# TP1_NodoWiFi_Pwr_Rev0.net
KiCad netlist of a schematic drawn in Altium Designer
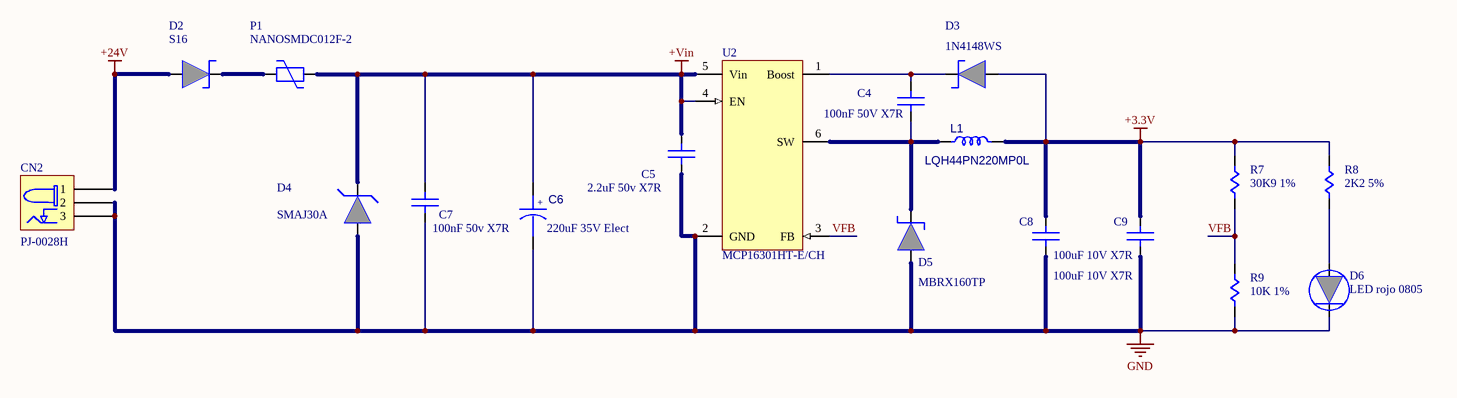
[diagram p0: TP1_NodoWiFi_Pwr_Rev0.SchDoc]

(export (version "E")
  (design (tool "Eeschema 10.0.6"))
  (components
    (comp (ref "C4")
      (value "100nF 50V X7R")
      (footprint "C_0805")
      (description "capacitor no polarizado")
      (libsource (lib "WifiNode") (part "Capacitor_NoP"))
    )
    (comp (ref "C5")
      (value "2.2uF 50v X7R")
      (footprint "C_0805")
      (description "capacitor no polarizado")
      (libsource (lib "WifiNode") (part "Capacitor_NoP"))
    )
    (comp (ref "C6")
      (value "220uF 35V Elect")
      (description "Polarized Capacitor")
      (libsource (lib "WifiNode") (part "CAP_P"))
    )
    (comp (ref "C7")
      (value "100nF 50v X7R")
      (footprint "C_0805")
      (description "capacitor no polarizado")
      (libsource (lib "WifiNode") (part "Capacitor_NoP"))
    )
    (comp (ref "C8")
      (value "100uF 10V X7R")
      (footprint "C_0805")
      (description "capacitor no polarizado")
      (libsource (lib "WifiNode") (part "Capacitor_NoP"))
    )
    (comp (ref "C9")
      (value "100uF 10V X7R")
      (footprint "C_0805")
      (description "capacitor no polarizado")
      (libsource (lib "WifiNode") (part "Capacitor_NoP"))
    )
    (comp (ref "CN2")
      (value "PJ-0028H")
      (footprint "PJ-002BH")
      (description "Conector PJ")
      (libsource (lib "WifiNode") (part "PJ-0028H"))
    )
    (comp (ref "D2")
      (value "S16")
      (footprint "Diode SOD-123")
      (description "Schottky")
      (libsource (lib "WifiNode") (part "Diodo Schottky"))
    )
    (comp (ref "D3")
      (value "1N4148WS")
      (footprint "Diode SOD-323")
      (description "Schottky")
      (libsource (lib "WifiNode") (part "Diodo Schottky"))
    )
    (comp (ref "D4")
      (value "SMAJ30A")
      (footprint "DO-214AC")
      (description "Zener")
      (libsource (lib "WifiNode") (part "Diodo Zener"))
    )
    (comp (ref "D5")
      (value "MBRX160TP")
      (footprint "Diode SOD-123")
      (description "Schottky")
      (libsource (lib "WifiNode") (part "Diodo Schottky"))
    )
    (comp (ref "D6")
      (value "LED rojo 0805")
      (footprint "D_0805")
      (description "LED")
      (libsource (lib "WifiNode") (part "Diodo LED"))
    )
    (comp (ref "L1")
      (value "LQH44PN220MP0L")
      (description "Inductor")
      (libsource (lib "WifiNode") (part "IND"))
    )
    (comp (ref "P1")
      (value "NANOSMDC012F-2")
      (footprint "Polyswitch 1206")
      (description "Poly Switch")
      (libsource (lib "WifiNode") (part "Poly Switch"))
    )
    (comp (ref "R7")
      (value "30K9 1%")
      (footprint "R_0805")
      (description "Resistor")
      (libsource (lib "WifiNode") (part "Resistencia"))
    )
    (comp (ref "R8")
      (value "2K2 5%")
      (footprint "R_0805")
      (description "Resistor")
      (libsource (lib "WifiNode") (part "Resistencia"))
    )
    (comp (ref "R9")
      (value "10K 1%")
      (footprint "R_0805")
      (description "Resistor")
      (libsource (lib "WifiNode") (part "Resistencia"))
    )
    (comp (ref "U2")
      (value "MCP16301HT-E/CH")
      (footprint "IC SOT23-6")
      (description "IC_DC/DC Buck controler")
      (libsource (lib "WifiNode") (part "MCP16301"))
    )
  )
  (nets
    (net (code "1") (name "+3.3V") (class "Default")
      (node (ref "C8") (pin "2") (pinfunction "Cap_2") (pintype "passive"))
      (node (ref "C9") (pin "2") (pinfunction "Cap_2") (pintype "passive"))
      (node (ref "D3") (pin "1") (pinfunction "Cap_1") (pintype "passive"))
      (node (ref "L1") (pin "2") (pinfunction "2_2") (pintype "passive"))
      (node (ref "R7") (pin "2") (pinfunction "Cap_2") (pintype "passive"))
      (node (ref "R8") (pin "2") (pinfunction "Cap_2") (pintype "passive"))
    )
    (net (code "2") (name "+24V") (class "Default")
      (node (ref "CN2") (pin "1") (pinfunction "1_1") (pintype "power_in"))
      (node (ref "D2") (pin "1") (pinfunction "Cap_1") (pintype "passive"))
    )
    (net (code "3") (name "+Vin") (class "Default")
      (node (ref "C5") (pin "2") (pinfunction "Cap_2") (pintype "passive"))
      (node (ref "C6") (pin "1") (pinfunction "1_1") (pintype "passive"))
      (node (ref "C7") (pin "2") (pinfunction "Cap_2") (pintype "passive"))
      (node (ref "D4") (pin "2") (pinfunction "Cap_2") (pintype "passive"))
      (node (ref "P1") (pin "1") (pinfunction "Cap_1") (pintype "passive"))
      (node (ref "U2") (pin "4") (pinfunction "EN_4") (pintype "input"))
      (node (ref "U2") (pin "5") (pinfunction "Vin_5") (pintype "power_in"))
    )
    (net (code "4") (name "/VFB") (class "Default")
      (node (ref "R7") (pin "1") (pinfunction "Cap_1") (pintype "passive"))
      (node (ref "R9") (pin "2") (pinfunction "Cap_2") (pintype "passive"))
      (node (ref "U2") (pin "3") (pinfunction "FB_3") (pintype "input"))
    )
    (net (code "5") (name "GND") (class "Default")
      (node (ref "C5") (pin "1") (pinfunction "Cap_1") (pintype "passive"))
      (node (ref "C6") (pin "2") (pinfunction "2_2") (pintype "passive"))
      (node (ref "C7") (pin "1") (pinfunction "Cap_1") (pintype "passive"))
      (node (ref "C8") (pin "1") (pinfunction "Cap_1") (pintype "passive"))
      (node (ref "C9") (pin "1") (pinfunction "Cap_1") (pintype "passive"))
      (node (ref "CN2") (pin "2") (pinfunction "2_2") (pintype "power_in"))
      (node (ref "CN2") (pin "3") (pinfunction "3_3") (pintype "power_in"))
      (node (ref "D4") (pin "1") (pinfunction "Cap_1") (pintype "passive"))
      (node (ref "D5") (pin "1") (pinfunction "Cap_1") (pintype "passive"))
      (node (ref "D6") (pin "2") (pinfunction "Cap_2") (pintype "passive"))
      (node (ref "R9") (pin "1") (pinfunction "Cap_1") (pintype "passive"))
      (node (ref "U2") (pin "2") (pinfunction "GND_2") (pintype "power_in"))
    )
    (net (code "6") (name "Net-(D2-Cap-Pad2)") (class "Default")
      (node (ref "D2") (pin "2") (pinfunction "Cap_2") (pintype "passive"))
      (node (ref "P1") (pin "2") (pinfunction "Cap_2") (pintype "passive"))
    )
    (net (code "7") (name "Net-(D6-Cap-Pad1)") (class "Default")
      (node (ref "D6") (pin "1") (pinfunction "Cap_1") (pintype "passive"))
      (node (ref "R8") (pin "1") (pinfunction "Cap_1") (pintype "passive"))
    )
    (net (code "8") (name "Net-(U2-Boost)") (class "Default")
      (node (ref "C4") (pin "2") (pinfunction "Cap_2") (pintype "passive"))
      (node (ref "D3") (pin "2") (pinfunction "Cap_2") (pintype "passive"))
      (node (ref "U2") (pin "1") (pinfunction "Boost_1") (pintype "passive"))
    )
    (net (code "9") (name "Net-(U2-SW)") (class "Default")
      (node (ref "C4") (pin "1") (pinfunction "Cap_1") (pintype "passive"))
      (node (ref "D5") (pin "2") (pinfunction "Cap_2") (pintype "passive"))
      (node (ref "L1") (pin "1") (pinfunction "1_1") (pintype "passive"))
      (node (ref "U2") (pin "6") (pinfunction "SW_6") (pintype "power_in"))
    )
  )
)
